# 04_LMS7002M_Digital.net
KiCad netlist of a schematic drawn in Altium Designer
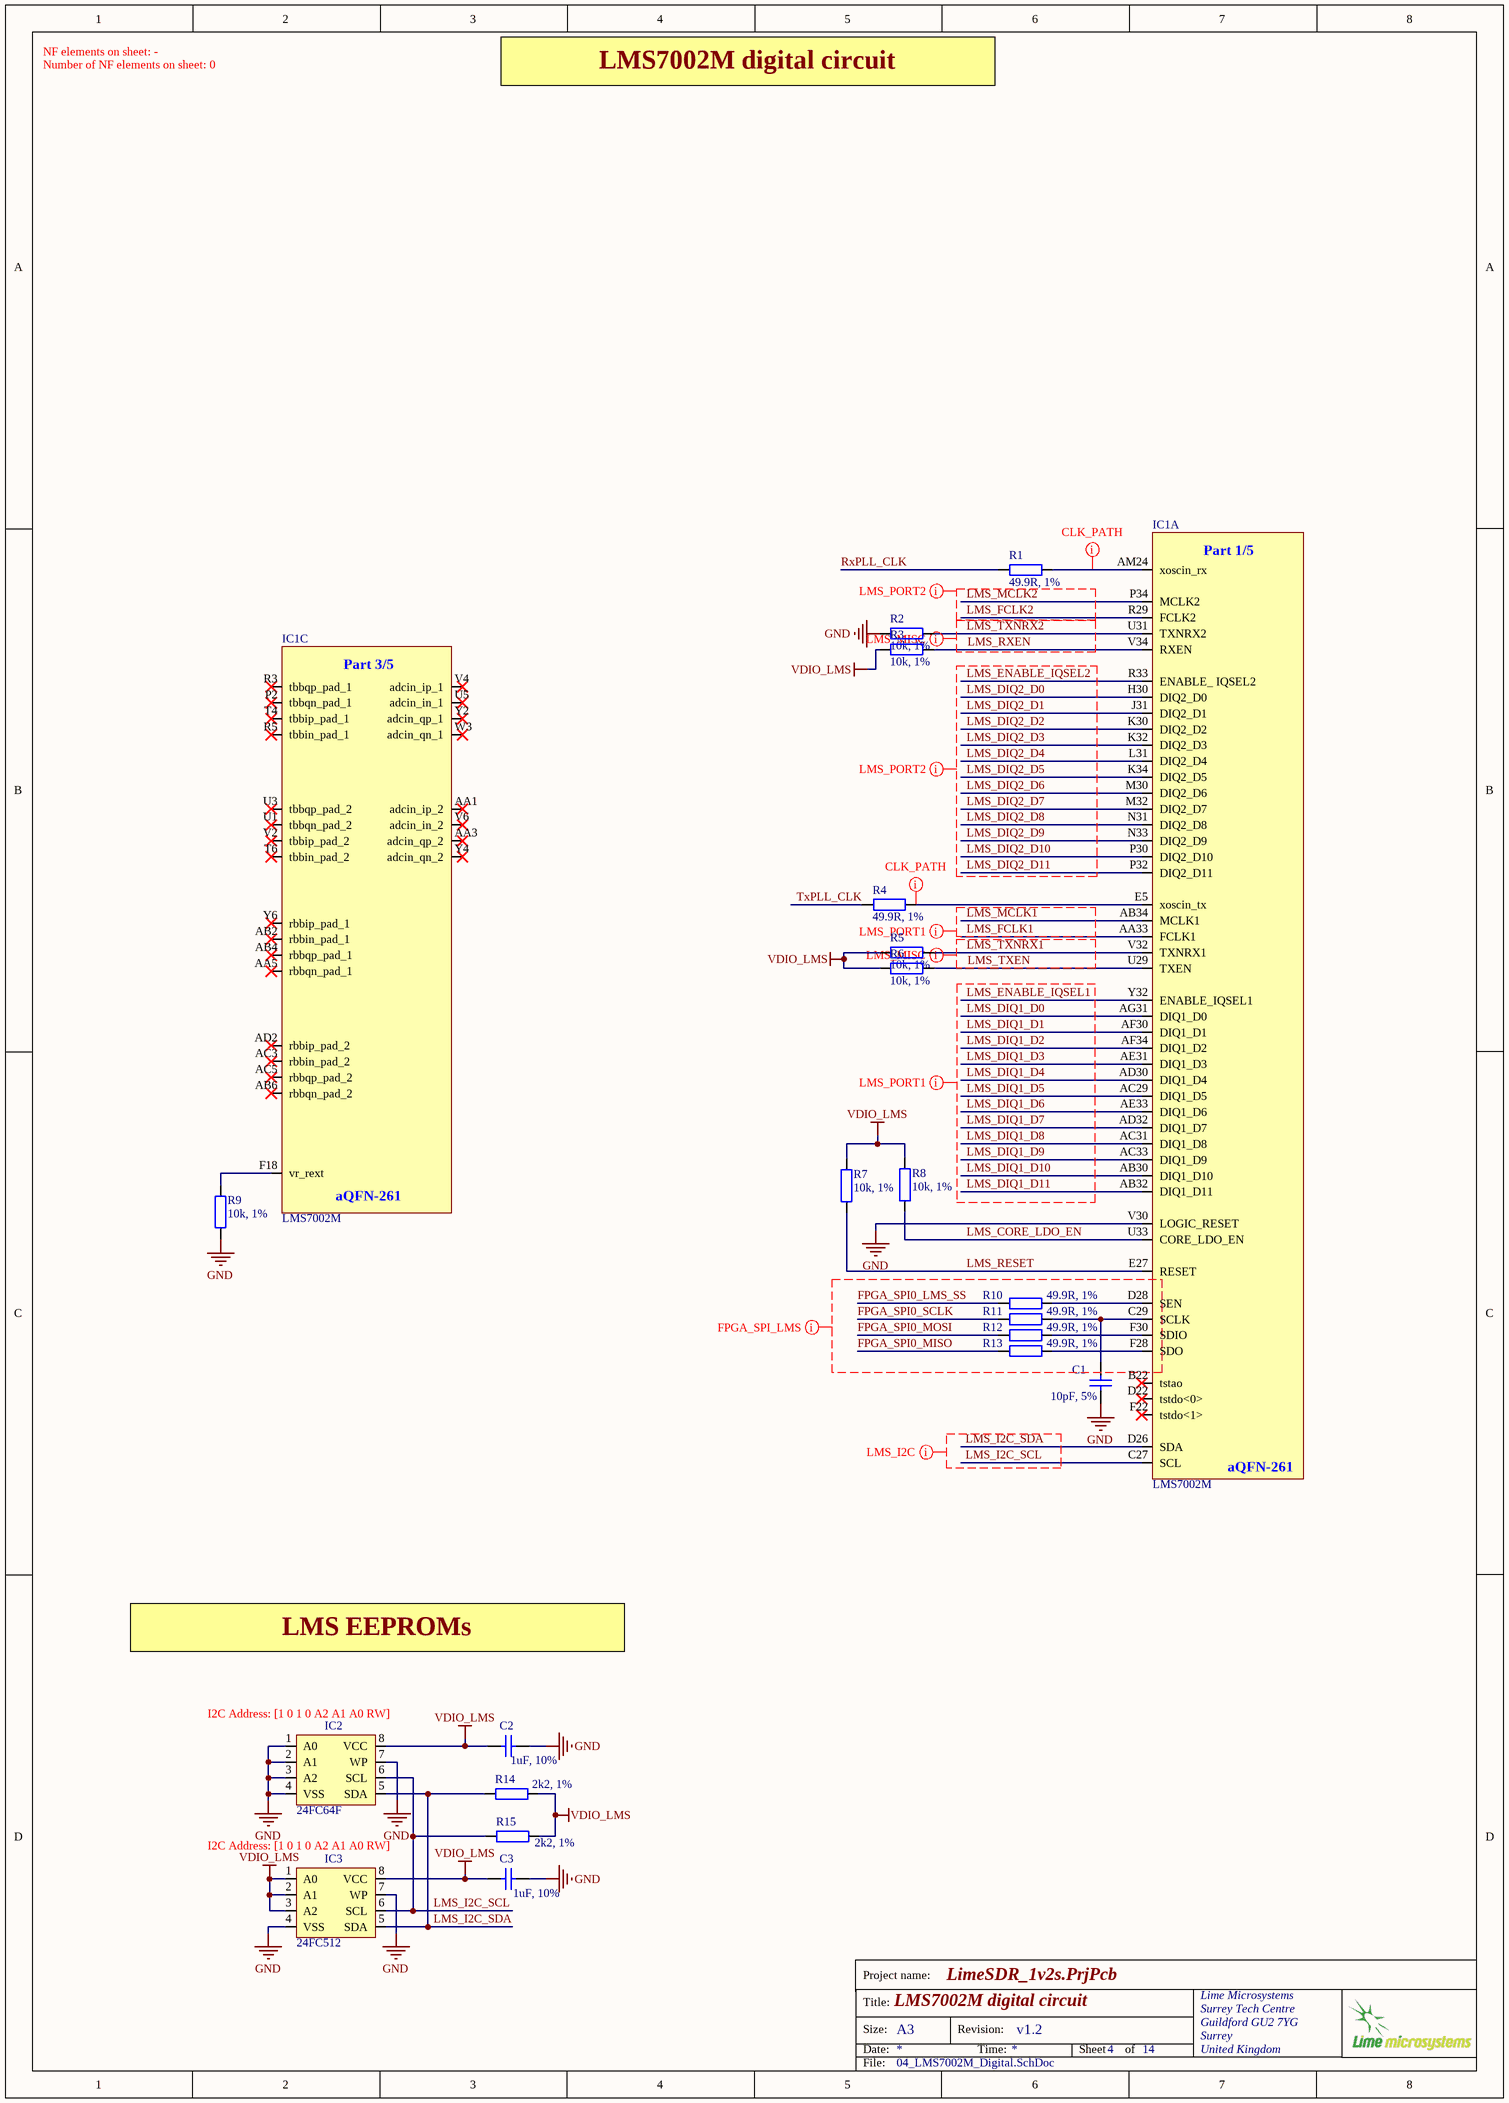
[diagram p0: 04_LMS7002M_Digital.SchDoc]

(export (version "E")
  (design (tool "Eeschema 10.0.6"))
  (components
    (comp (ref "C1")
      (value "10pF, 5%")
      (footprint "CAP0402")
      (fields (field (name "MANUFACTURER") "AVX"))
      (libsource (lib "LimeMicroAltiumLib_schLib") (part "Cap_0402"))
    )
    (comp (ref "C2")
      (value "1uF, 10%")
      (footprint "CAP0402")
      (fields (field (name "MANUFACTURER") "TDK"))
      (libsource (lib "LimeMicroAltiumLib_schLib") (part "Cap_0402"))
    )
    (comp (ref "C3")
      (value "1uF, 10%")
      (footprint "CAP0402")
      (fields (field (name "MANUFACTURER") "TDK"))
      (libsource (lib "LimeMicroAltiumLib_schLib") (part "Cap_0402"))
    )
    (comp (ref "IC1")
      (value "LMS7002M")
      (footprint "LMS7002M")
      (fields (field (name "MANUFACTURER") "Lime Microsystems"))
      (libsource (lib "") (part "LMS7002M_1"))
    )
    (comp (ref "IC2")
      (value "24FC64F")
      (footprint "24FC512")
      (fields (field (name "MANUFACTURER") "Microchip Technology"))
      (libsource (lib "LimeMicroAltiumLib_schLib") (part "24FC64F"))
    )
    (comp (ref "IC3")
      (value "24FC512")
      (footprint "24FC512")
      (fields (field (name "MANUFACTURER") "Microchip Technology"))
      (libsource (lib "LimeMicroAltiumLib_schLib") (part "24FC512"))
    )
    (comp (ref "R1")
      (value "49.9R, 1%")
      (footprint "LimeMicroAltiumLib_pcbLib:RES0402")
      (fields
        (field (name "TOLERANCE") "±1%")
        (field (name "MANUFACTURER") "Samsung Electro-Mechanics America, Inc.")
        (field (name "MANUFACTURER PART NUMBER") "RC1005F49R9CS")
      )
      (libsource (lib "LimeMicroAltiumLib_schLib") (part "Res_0402"))
    )
    (comp (ref "R2")
      (value "10k, 1%")
      (footprint "RES0402")
      (fields (field (name "MANUFACTURER") "Yageo") (field (name "TOLERANCE") "±1%"))
      (libsource (lib "LimeMicroAltiumLib_schLib") (part "Res_0402"))
    )
    (comp (ref "R3")
      (value "10k, 1%")
      (footprint "RES0402")
      (fields (field (name "MANUFACTURER") "Yageo") (field (name "TOLERANCE") "±1%"))
      (libsource (lib "LimeMicroAltiumLib_schLib") (part "Res_0402"))
    )
    (comp (ref "R4")
      (value "49.9R, 1%")
      (footprint "LimeMicroAltiumLib_pcbLib:RES0402")
      (fields
        (field (name "TOLERANCE") "±1%")
        (field (name "MANUFACTURER") "Samsung Electro-Mechanics America, Inc.")
        (field (name "MANUFACTURER PART NUMBER") "RC1005F49R9CS")
      )
      (libsource (lib "LimeMicroAltiumLib_schLib") (part "Res_0402"))
    )
    (comp (ref "R5")
      (value "10k, 1%")
      (footprint "RES0402")
      (fields (field (name "MANUFACTURER") "Yageo") (field (name "TOLERANCE") "±1%"))
      (libsource (lib "LimeMicroAltiumLib_schLib") (part "Res_0402"))
    )
    (comp (ref "R6")
      (value "10k, 1%")
      (footprint "RES0402")
      (fields (field (name "MANUFACTURER") "Yageo") (field (name "TOLERANCE") "±1%"))
      (libsource (lib "LimeMicroAltiumLib_schLib") (part "Res_0402"))
    )
    (comp (ref "R7")
      (value "10k, 1%")
      (footprint "RES0402")
      (fields (field (name "MANUFACTURER") "Yageo") (field (name "TOLERANCE") "±1%"))
      (libsource (lib "LimeMicroAltiumLib_schLib") (part "Res_0402"))
    )
    (comp (ref "R8")
      (value "10k, 1%")
      (footprint "RES0402")
      (fields (field (name "MANUFACTURER") "Yageo") (field (name "TOLERANCE") "±1%"))
      (libsource (lib "LimeMicroAltiumLib_schLib") (part "Res_0402"))
    )
    (comp (ref "R9")
      (value "10k, 1%")
      (footprint "RES0402")
      (fields (field (name "MANUFACTURER") "Yageo") (field (name "TOLERANCE") "±1%"))
      (libsource (lib "LimeMicroAltiumLib_schLib") (part "Res_0402"))
    )
    (comp (ref "R10")
      (value "49.9R, 1%")
      (footprint "LimeMicroAltiumLib_pcbLib:RES0402")
      (fields
        (field (name "TOLERANCE") "±1%")
        (field (name "MANUFACTURER") "Samsung Electro-Mechanics America, Inc.")
        (field (name "MANUFACTURER PART NUMBER") "RC1005F49R9CS")
      )
      (libsource (lib "LimeMicroAltiumLib_schLib") (part "Res_0402"))
    )
    (comp (ref "R11")
      (value "49.9R, 1%")
      (footprint "LimeMicroAltiumLib_pcbLib:RES0402")
      (fields
        (field (name "TOLERANCE") "±1%")
        (field (name "MANUFACTURER") "Samsung Electro-Mechanics America, Inc.")
        (field (name "MANUFACTURER PART NUMBER") "RC1005F49R9CS")
      )
      (libsource (lib "LimeMicroAltiumLib_schLib") (part "Res_0402"))
    )
    (comp (ref "R12")
      (value "49.9R, 1%")
      (footprint "LimeMicroAltiumLib_pcbLib:RES0402")
      (fields
        (field (name "TOLERANCE") "±1%")
        (field (name "MANUFACTURER") "Samsung Electro-Mechanics America, Inc.")
        (field (name "MANUFACTURER PART NUMBER") "RC1005F49R9CS")
      )
      (libsource (lib "LimeMicroAltiumLib_schLib") (part "Res_0402"))
    )
    (comp (ref "R13")
      (value "49.9R, 1%")
      (footprint "LimeMicroAltiumLib_pcbLib:RES0402")
      (fields
        (field (name "TOLERANCE") "±1%")
        (field (name "MANUFACTURER") "Samsung Electro-Mechanics America, Inc.")
        (field (name "MANUFACTURER PART NUMBER") "RC1005F49R9CS")
      )
      (libsource (lib "LimeMicroAltiumLib_schLib") (part "Res_0402"))
    )
    (comp (ref "R14")
      (value "2k2, 1%")
      (footprint "RES0402")
      (fields (field (name "MANUFACTURER") "Stackpole Electronics Inc") (field (name "TOLERANCE") "±1%"))
      (libsource (lib "LimeMicroAltiumLib_schLib") (part "Res_0402"))
    )
    (comp (ref "R15")
      (value "2k2, 1%")
      (footprint "RES0402")
      (fields (field (name "MANUFACTURER") "Stackpole Electronics Inc") (field (name "TOLERANCE") "±1%"))
      (libsource (lib "LimeMicroAltiumLib_schLib") (part "Res_0402"))
    )
  )
  (nets
    (net (code "1") (name "/FPGA_SPI0_LMS_SS") (class "Default")
      (node (ref "R10") (pin "2") (pinfunction "2_2") (pintype "passive"))
    )
    (net (code "2") (name "/FPGA_SPI0_MISO") (class "Default")
      (node (ref "R13") (pin "2") (pinfunction "2_2") (pintype "passive"))
    )
    (net (code "3") (name "/FPGA_SPI0_MOSI") (class "Default")
      (node (ref "R12") (pin "2") (pinfunction "2_2") (pintype "passive"))
    )
    (net (code "4") (name "/FPGA_SPI0_SCLK") (class "Default")
      (node (ref "R11") (pin "2") (pinfunction "2_2") (pintype "passive"))
    )
    (net (code "5") (name "/LMS_CORE_LDO_EN") (class "Default")
      (node (ref "IC1") (pin "U33") (pinfunction "CORE_LDO_EN_U33") (pintype "passive"))
      (node (ref "R8") (pin "1") (pinfunction "1_1") (pintype "passive"))
    )
    (net (code "6") (name "/LMS_DIQ1_D0") (class "Default")
      (node (ref "IC1") (pin "AG31") (pinfunction "DIQ1_D0_AG31") (pintype "passive"))
    )
    (net (code "7") (name "/LMS_DIQ1_D1") (class "Default")
      (node (ref "IC1") (pin "AF30") (pinfunction "DIQ1_D1_AF30") (pintype "passive"))
    )
    (net (code "8") (name "/LMS_DIQ1_D2") (class "Default")
      (node (ref "IC1") (pin "AF34") (pinfunction "DIQ1_D2_AF34") (pintype "passive"))
    )
    (net (code "9") (name "/LMS_DIQ1_D3") (class "Default")
      (node (ref "IC1") (pin "AE31") (pinfunction "DIQ1_D3_AE31") (pintype "passive"))
    )
    (net (code "10") (name "/LMS_DIQ1_D4") (class "Default")
      (node (ref "IC1") (pin "AD30") (pinfunction "DIQ1_D4_AD30") (pintype "passive"))
    )
    (net (code "11") (name "/LMS_DIQ1_D5") (class "Default")
      (node (ref "IC1") (pin "AC29") (pinfunction "DIQ1_D5_AC29") (pintype "passive"))
    )
    (net (code "12") (name "/LMS_DIQ1_D6") (class "Default")
      (node (ref "IC1") (pin "AE33") (pinfunction "DIQ1_D6_AE33") (pintype "passive"))
    )
    (net (code "13") (name "/LMS_DIQ1_D7") (class "Default")
      (node (ref "IC1") (pin "AD32") (pinfunction "DIQ1_D7_AD32") (pintype "passive"))
    )
    (net (code "14") (name "/LMS_DIQ1_D8") (class "Default")
      (node (ref "IC1") (pin "AC31") (pinfunction "DIQ1_D8_AC31") (pintype "passive"))
    )
    (net (code "15") (name "/LMS_DIQ1_D9") (class "Default")
      (node (ref "IC1") (pin "AC33") (pinfunction "DIQ1_D9_AC33") (pintype "passive"))
    )
    (net (code "16") (name "/LMS_DIQ1_D10") (class "Default")
      (node (ref "IC1") (pin "AB30") (pinfunction "DIQ1_D10_AB30") (pintype "passive"))
    )
    (net (code "17") (name "/LMS_DIQ1_D11") (class "Default")
      (node (ref "IC1") (pin "AB32") (pinfunction "DIQ1_D11_AB32") (pintype "passive"))
    )
    (net (code "18") (name "/LMS_DIQ2_D0") (class "Default")
      (node (ref "IC1") (pin "H30") (pinfunction "DIQ2_D0_H30") (pintype "passive"))
    )
    (net (code "19") (name "/LMS_DIQ2_D1") (class "Default")
      (node (ref "IC1") (pin "J31") (pinfunction "DIQ2_D1_J31") (pintype "passive"))
    )
    (net (code "20") (name "/LMS_DIQ2_D2") (class "Default")
      (node (ref "IC1") (pin "K30") (pinfunction "DIQ2_D2_K30") (pintype "passive"))
    )
    (net (code "21") (name "/LMS_DIQ2_D3") (class "Default")
      (node (ref "IC1") (pin "K32") (pinfunction "DIQ2_D3_K32") (pintype "passive"))
    )
    (net (code "22") (name "/LMS_DIQ2_D4") (class "Default")
      (node (ref "IC1") (pin "L31") (pinfunction "DIQ2_D4_L31") (pintype "passive"))
    )
    (net (code "23") (name "/LMS_DIQ2_D5") (class "Default")
      (node (ref "IC1") (pin "K34") (pinfunction "DIQ2_D5_K34") (pintype "passive"))
    )
    (net (code "24") (name "/LMS_DIQ2_D6") (class "Default")
      (node (ref "IC1") (pin "M30") (pinfunction "DIQ2_D6_M30") (pintype "passive"))
    )
    (net (code "25") (name "/LMS_DIQ2_D7") (class "Default")
      (node (ref "IC1") (pin "M32") (pinfunction "DIQ2_D7_M32") (pintype "passive"))
    )
    (net (code "26") (name "/LMS_DIQ2_D8") (class "Default")
      (node (ref "IC1") (pin "N31") (pinfunction "DIQ2_D8_N31") (pintype "passive"))
    )
    (net (code "27") (name "/LMS_DIQ2_D9") (class "Default")
      (node (ref "IC1") (pin "N33") (pinfunction "DIQ2_D9_N33") (pintype "passive"))
    )
    (net (code "28") (name "/LMS_DIQ2_D10") (class "Default")
      (node (ref "IC1") (pin "P30") (pinfunction "DIQ2_D10_P30") (pintype "passive"))
    )
    (net (code "29") (name "/LMS_DIQ2_D11") (class "Default")
      (node (ref "IC1") (pin "P32") (pinfunction "DIQ2_D11_P32") (pintype "passive"))
    )
    (net (code "30") (name "/LMS_ENABLE_IQSEL1") (class "Default")
      (node (ref "IC1") (pin "Y32") (pinfunction "ENABLE_IQSEL1_Y32") (pintype "passive"))
    )
    (net (code "31") (name "/LMS_ENABLE_IQSEL2") (class "Default")
      (node (ref "IC1") (pin "R33") (pinfunction "ENABLE__IQSEL2_R33") (pintype "passive"))
    )
    (net (code "32") (name "/LMS_FCLK1") (class "Default")
      (node (ref "IC1") (pin "AA33") (pinfunction "FCLK1_AA33") (pintype "passive"))
    )
    (net (code "33") (name "/LMS_FCLK2") (class "Default")
      (node (ref "IC1") (pin "R29") (pinfunction "FCLK2_R29") (pintype "passive"))
    )
    (net (code "34") (name "/LMS_I2C_SCL") (class "Default")
      (node (ref "IC1") (pin "C27") (pinfunction "SCL_C27") (pintype "passive"))
      (node (ref "IC2") (pin "6") (pinfunction "SCL_6") (pintype "passive"))
      (node (ref "IC3") (pin "6") (pinfunction "SCL_6") (pintype "passive"))
      (node (ref "R15") (pin "2") (pinfunction "2_2") (pintype "passive"))
    )
    (net (code "35") (name "/LMS_I2C_SDA") (class "Default")
      (node (ref "IC1") (pin "D26") (pinfunction "SDA_D26") (pintype "passive"))
      (node (ref "IC2") (pin "5") (pinfunction "SDA_5") (pintype "passive"))
      (node (ref "IC3") (pin "5") (pinfunction "SDA_5") (pintype "passive"))
      (node (ref "R14") (pin "2") (pinfunction "2_2") (pintype "passive"))
    )
    (net (code "36") (name "/LMS_MCLK1") (class "Default")
      (node (ref "IC1") (pin "AB34") (pinfunction "MCLK1_AB34") (pintype "passive"))
    )
    (net (code "37") (name "/LMS_MCLK2") (class "Default")
      (node (ref "IC1") (pin "P34") (pinfunction "MCLK2_P34") (pintype "passive"))
    )
    (net (code "38") (name "/LMS_RESET") (class "Default")
      (node (ref "IC1") (pin "E27") (pinfunction "RESET_E27") (pintype "passive"))
      (node (ref "R7") (pin "1") (pinfunction "1_1") (pintype "passive"))
    )
    (net (code "39") (name "/LMS_RXEN") (class "Default")
      (node (ref "IC1") (pin "V34") (pinfunction "RXEN_V34") (pintype "passive"))
      (node (ref "R3") (pin "2") (pinfunction "2_2") (pintype "passive"))
    )
    (net (code "40") (name "/LMS_TXEN") (class "Default")
      (node (ref "IC1") (pin "U29") (pinfunction "TXEN_U29") (pintype "passive"))
      (node (ref "R6") (pin "2") (pinfunction "2_2") (pintype "passive"))
    )
    (net (code "41") (name "/LMS_TXNRX1") (class "Default")
      (node (ref "IC1") (pin "V32") (pinfunction "TXNRX1_V32") (pintype "passive"))
      (node (ref "R5") (pin "2") (pinfunction "2_2") (pintype "passive"))
    )
    (net (code "42") (name "/LMS_TXNRX2") (class "Default")
      (node (ref "IC1") (pin "U31") (pinfunction "TXNRX2_U31") (pintype "passive"))
      (node (ref "R2") (pin "2") (pinfunction "2_2") (pintype "passive"))
    )
    (net (code "43") (name "/RxPLL_CLK") (class "Default")
      (node (ref "R1") (pin "2") (pinfunction "2_2") (pintype "passive"))
    )
    (net (code "44") (name "/TxPLL_CLK") (class "Default")
      (node (ref "R4") (pin "2") (pinfunction "2_2") (pintype "passive"))
    )
    (net (code "45") (name "GND") (class "Default")
      (node (ref "C1") (pin "2") (pinfunction "2_2") (pintype "passive"))
      (node (ref "C2") (pin "1") (pinfunction "1_1") (pintype "passive"))
      (node (ref "C3") (pin "1") (pinfunction "1_1") (pintype "passive"))
      (node (ref "IC1") (pin "V30") (pinfunction "LOGIC_RESET_V30") (pintype "passive"))
      (node (ref "IC2") (pin "1") (pinfunction "A0_1") (pintype "passive"))
      (node (ref "IC2") (pin "2") (pinfunction "A1_2") (pintype "passive"))
      (node (ref "IC2") (pin "3") (pinfunction "A2_3") (pintype "passive"))
      (node (ref "IC2") (pin "4") (pinfunction "VSS_4") (pintype "passive"))
      (node (ref "IC2") (pin "7") (pinfunction "WP_7") (pintype "passive"))
      (node (ref "IC3") (pin "4") (pinfunction "VSS_4") (pintype "passive"))
      (node (ref "IC3") (pin "7") (pinfunction "WP_7") (pintype "passive"))
      (node (ref "R2") (pin "1") (pinfunction "1_1") (pintype "passive"))
      (node (ref "R9") (pin "2") (pinfunction "2_2") (pintype "passive"))
    )
    (net (code "46") (name "Net-(IC1A-SCLK)") (class "Default")
      (node (ref "C1") (pin "1") (pinfunction "1_1") (pintype "passive"))
      (node (ref "IC1") (pin "C29") (pinfunction "SCLK_C29") (pintype "passive"))
      (node (ref "R11") (pin "1") (pinfunction "1_1") (pintype "passive"))
    )
    (net (code "47") (name "Net-(IC1A-SDIO)") (class "Default")
      (node (ref "IC1") (pin "F30") (pinfunction "SDIO_F30") (pintype "passive"))
      (node (ref "R12") (pin "1") (pinfunction "1_1") (pintype "passive"))
    )
    (net (code "48") (name "Net-(IC1A-SDO)") (class "Default")
      (node (ref "IC1") (pin "F28") (pinfunction "SDO_F28") (pintype "passive"))
      (node (ref "R13") (pin "1") (pinfunction "1_1") (pintype "passive"))
    )
    (net (code "49") (name "Net-(IC1A-SEN)") (class "Default")
      (node (ref "IC1") (pin "D28") (pinfunction "SEN_D28") (pintype "passive"))
      (node (ref "R10") (pin "1") (pinfunction "1_1") (pintype "passive"))
    )
    (net (code "50") (name "Net-(IC1A-xoscin_rx)") (class "Default")
      (node (ref "IC1") (pin "AM24") (pinfunction "xoscin_rx_AM24") (pintype "passive"))
      (node (ref "R1") (pin "1") (pinfunction "1_1") (pintype "passive"))
    )
    (net (code "51") (name "Net-(IC1A-xoscin_tx)") (class "Default")
      (node (ref "IC1") (pin "E5") (pinfunction "xoscin_tx_E5") (pintype "passive"))
      (node (ref "R4") (pin "1") (pinfunction "1_1") (pintype "passive"))
    )
    (net (code "52") (name "Net-(IC1C-vr_rext)") (class "Default")
      (node (ref "IC1") (pin "F18") (pinfunction "vr_rext_F18") (pintype "passive"))
      (node (ref "R9") (pin "1") (pinfunction "1_1") (pintype "passive"))
    )
    (net (code "53") (name "VDIO_LMS") (class "Default")
      (node (ref "C2") (pin "2") (pinfunction "2_2") (pintype "passive"))
      (node (ref "C3") (pin "2") (pinfunction "2_2") (pintype "passive"))
      (node (ref "IC2") (pin "8") (pinfunction "VCC_8") (pintype "passive"))
      (node (ref "IC3") (pin "1") (pinfunction "A0_1") (pintype "passive"))
      (node (ref "IC3") (pin "2") (pinfunction "A1_2") (pintype "passive"))
      (node (ref "IC3") (pin "3") (pinfunction "A2_3") (pintype "passive"))
      (node (ref "IC3") (pin "8") (pinfunction "VCC_8") (pintype "passive"))
      (node (ref "R14") (pin "1") (pinfunction "1_1") (pintype "passive"))
      (node (ref "R15") (pin "1") (pinfunction "1_1") (pintype "passive"))
      (node (ref "R3") (pin "1") (pinfunction "1_1") (pintype "passive"))
      (node (ref "R5") (pin "1") (pinfunction "1_1") (pintype "passive"))
      (node (ref "R6") (pin "1") (pinfunction "1_1") (pintype "passive"))
      (node (ref "R7") (pin "2") (pinfunction "2_2") (pintype "passive"))
      (node (ref "R8") (pin "2") (pinfunction "2_2") (pintype "passive"))
    )
    (net (code "54") (name "unconnected-(IC1A-tstao-PadB22)") (class "Default")
      (node (ref "IC1") (pin "B22") (pinfunction "tstao_B22") (pintype "passive+no_connect"))
    )
    (net (code "55") (name "unconnected-(IC1A-tstdo<0>-PadD22)") (class "Default")
      (node (ref "IC1") (pin "D22") (pinfunction "tstdo<0>_D22") (pintype "passive+no_connect"))
    )
    (net (code "56") (name "unconnected-(IC1A-tstdo<1>-PadF22)") (class "Default")
      (node (ref "IC1") (pin "F22") (pinfunction "tstdo<1>_F22") (pintype "passive+no_connect"))
    )
    (net (code "57") (name "unconnected-(IC1C-adcin_in_1-PadU5)") (class "Default")
      (node (ref "IC1") (pin "U5") (pinfunction "adcin_in_1_U5") (pintype "passive+no_connect"))
    )
    (net (code "58") (name "unconnected-(IC1C-adcin_in_2-PadV6)") (class "Default")
      (node (ref "IC1") (pin "V6") (pinfunction "adcin_in_2_V6") (pintype "passive+no_connect"))
    )
    (net (code "59") (name "unconnected-(IC1C-adcin_ip_1-PadV4)") (class "Default")
      (node (ref "IC1") (pin "V4") (pinfunction "adcin_ip_1_V4") (pintype "passive+no_connect"))
    )
    (net (code "60") (name "unconnected-(IC1C-adcin_ip_2-PadAA1)") (class "Default")
      (node (ref "IC1") (pin "AA1") (pinfunction "adcin_ip_2_AA1") (pintype "passive+no_connect"))
    )
    (net (code "61") (name "unconnected-(IC1C-adcin_qn_1-PadW3)") (class "Default")
      (node (ref "IC1") (pin "W3") (pinfunction "adcin_qn_1_W3") (pintype "passive+no_connect"))
    )
    (net (code "62") (name "unconnected-(IC1C-adcin_qn_2-PadY4)") (class "Default")
      (node (ref "IC1") (pin "Y4") (pinfunction "adcin_qn_2_Y4") (pintype "passive+no_connect"))
    )
    (net (code "63") (name "unconnected-(IC1C-adcin_qp_1-PadY2)") (class "Default")
      (node (ref "IC1") (pin "Y2") (pinfunction "adcin_qp_1_Y2") (pintype "passive+no_connect"))
    )
    (net (code "64") (name "unconnected-(IC1C-adcin_qp_2-PadAA3)") (class "Default")
      (node (ref "IC1") (pin "AA3") (pinfunction "adcin_qp_2_AA3") (pintype "passive+no_connect"))
    )
    (net (code "65") (name "unconnected-(IC1C-rbbin_pad_1-PadAB2)") (class "Default")
      (node (ref "IC1") (pin "AB2") (pinfunction "rbbin_pad_1_AB2") (pintype "passive+no_connect"))
    )
    (net (code "66") (name "unconnected-(IC1C-rbbin_pad_2-PadAC3)") (class "Default")
      (node (ref "IC1") (pin "AC3") (pinfunction "rbbin_pad_2_AC3") (pintype "passive+no_connect"))
    )
    (net (code "67") (name "unconnected-(IC1C-rbbip_pad_1-PadY6)") (class "Default")
      (node (ref "IC1") (pin "Y6") (pinfunction "rbbip_pad_1_Y6") (pintype "passive+no_connect"))
    )
    (net (code "68") (name "unconnected-(IC1C-rbbip_pad_2-PadAD2)") (class "Default")
      (node (ref "IC1") (pin "AD2") (pinfunction "rbbip_pad_2_AD2") (pintype "passive+no_connect"))
    )
    (net (code "69") (name "unconnected-(IC1C-rbbqn_pad_1-PadAA5)") (class "Default")
      (node (ref "IC1") (pin "AA5") (pinfunction "rbbqn_pad_1_AA5") (pintype "passive+no_connect"))
    )
    (net (code "70") (name "unconnected-(IC1C-rbbqn_pad_2-PadAB6)") (class "Default")
      (node (ref "IC1") (pin "AB6") (pinfunction "rbbqn_pad_2_AB6") (pintype "passive+no_connect"))
    )
    (net (code "71") (name "unconnected-(IC1C-rbbqp_pad_1-PadAB4)") (class "Default")
      (node (ref "IC1") (pin "AB4") (pinfunction "rbbqp_pad_1_AB4") (pintype "passive+no_connect"))
    )
    (net (code "72") (name "unconnected-(IC1C-rbbqp_pad_2-PadAC5)") (class "Default")
      (node (ref "IC1") (pin "AC5") (pinfunction "rbbqp_pad_2_AC5") (pintype "passive+no_connect"))
    )
    (net (code "73") (name "unconnected-(IC1C-tbbin_pad_1-PadR5)") (class "Default")
      (node (ref "IC1") (pin "R5") (pinfunction "tbbin_pad_1_R5") (pintype "passive+no_connect"))
    )
    (net (code "74") (name "unconnected-(IC1C-tbbin_pad_2-PadT6)") (class "Default")
      (node (ref "IC1") (pin "T6") (pinfunction "tbbin_pad_2_T6") (pintype "passive+no_connect"))
    )
    (net (code "75") (name "unconnected-(IC1C-tbbip_pad_1-PadT4)") (class "Default")
      (node (ref "IC1") (pin "T4") (pinfunction "tbbip_pad_1_T4") (pintype "passive+no_connect"))
    )
    (net (code "76") (name "unconnected-(IC1C-tbbip_pad_2-PadV2)") (class "Default")
      (node (ref "IC1") (pin "V2") (pinfunction "tbbip_pad_2_V2") (pintype "passive+no_connect"))
    )
    (net (code "77") (name "unconnected-(IC1C-tbbqn_pad_1-PadP2)") (class "Default")
      (node (ref "IC1") (pin "P2") (pinfunction "tbbqn_pad_1_P2") (pintype "passive+no_connect"))
    )
    (net (code "78") (name "unconnected-(IC1C-tbbqn_pad_2-PadU1)") (class "Default")
      (node (ref "IC1") (pin "U1") (pinfunction "tbbqn_pad_2_U1") (pintype "passive+no_connect"))
    )
    (net (code "79") (name "unconnected-(IC1C-tbbqp_pad_1-PadR3)") (class "Default")
      (node (ref "IC1") (pin "R3") (pinfunction "tbbqp_pad_1_R3") (pintype "passive+no_connect"))
    )
    (net (code "80") (name "unconnected-(IC1C-tbbqp_pad_2-PadU3)") (class "Default")
      (node (ref "IC1") (pin "U3") (pinfunction "tbbqp_pad_2_U3") (pintype "passive+no_connect"))
    )
  )
)
